# SI4432_Transceiver.net
KiCad netlist of a schematic drawn in Altium Designer
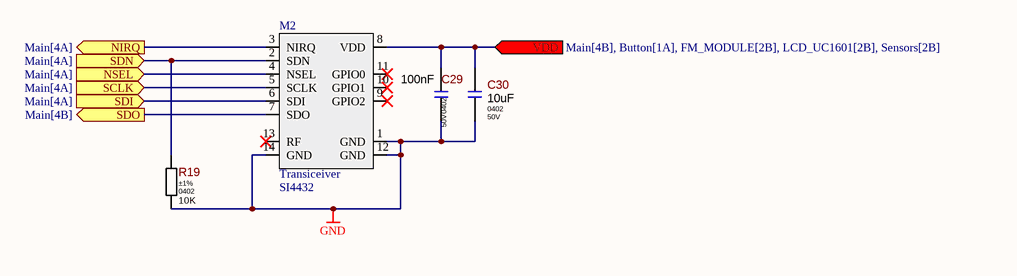
[diagram p0: SI4432_Transceiver.SchDoc]

(export (version "E")
  (design (tool "Eeschema 10.0.6"))
  (components
    (comp (ref "C29")
      (value "100nF")
      (footprint "Cap_0402")
      (description "100nF 50V  ±25% 0402 Ceramic Capacitor")
      (fields
        (field (name "TOLERANCE") "±25%")
        (field (name "PACKAGE") "0402")
        (field (name "VOLTAGE") "50V")
      )
      (libsource (lib "Capacitors") (part "Cap_0402_100nF"))
    )
    (comp (ref "C30")
      (value "10uF")
      (footprint "Cap_0402")
      (description "10uF 50V  ±25% 0402 Ceramic Capacitor")
      (fields
        (field (name "TOLERANCE") "±25%")
        (field (name "PACKAGE") "0402")
        (field (name "VOLTAGE") "50V")
      )
      (libsource (lib "Capacitors") (part "Cap_0402_10uF"))
    )
    (comp (ref "M2")
      (value "Transiceiver")
      (footprint "SI4432")
      (fields (field (name "NAME") "SI4432"))
      (libsource (lib "Module") (part "SI4432"))
    )
    (comp (ref "R19")
      (value "10K")
      (footprint "Res_0402")
      (description "±1% 1/16W 0402")
      (fields
        (field (name "VOLTAGE") "50V")
        (field (name "TOLERANCE") "±1%")
        (field (name "PACKAGE") "0402")
        (field (name "Comment") "Res_0402_10K")
      )
      (libsource (lib "Resistors") (part "Res_0402_10K"))
    )
  )
  (nets
    (net (code "1") (name "/NIRQ") (class "Default")
      (node (ref "M2") (pin "3") (pinfunction "NIRQ_3") (pintype "passive"))
    )
    (net (code "2") (name "/NSEL") (class "Default")
      (node (ref "M2") (pin "4") (pinfunction "NSEL_4") (pintype "passive"))
    )
    (net (code "3") (name "/SCLK") (class "Default")
      (node (ref "M2") (pin "5") (pinfunction "SCLK_5") (pintype "passive"))
    )
    (net (code "4") (name "/SDI") (class "Default")
      (node (ref "M2") (pin "6") (pinfunction "SDI_6") (pintype "passive"))
    )
    (net (code "5") (name "/SDN") (class "Default")
      (node (ref "M2") (pin "2") (pinfunction "SDN_2") (pintype "passive"))
      (node (ref "R19") (pin "1") (pintype "passive"))
    )
    (net (code "6") (name "/SDO") (class "Default")
      (node (ref "M2") (pin "7") (pinfunction "SDO_7") (pintype "passive"))
    )
    (net (code "7") (name "/VDD") (class "Default")
      (node (ref "C29") (pin "1") (pinfunction "1_1") (pintype "passive"))
      (node (ref "C30") (pin "1") (pinfunction "1_1") (pintype "passive"))
      (node (ref "M2") (pin "8") (pinfunction "VDD_8") (pintype "passive"))
    )
    (net (code "8") (name "GND") (class "Default")
      (node (ref "C29") (pin "2") (pinfunction "2_2") (pintype "passive"))
      (node (ref "C30") (pin "2") (pinfunction "2_2") (pintype "passive"))
      (node (ref "M2") (pin "1") (pinfunction "GND_1") (pintype "passive"))
      (node (ref "M2") (pin "12") (pinfunction "GND_12") (pintype "passive"))
      (node (ref "M2") (pin "14") (pinfunction "GND_14") (pintype "passive"))
      (node (ref "R19") (pin "2") (pintype "passive"))
    )
    (net (code "9") (name "unconnected-(M2-GPIO0-Pad11)") (class "Default")
      (node (ref "M2") (pin "11") (pinfunction "GPIO0_11") (pintype "passive+no_connect"))
    )
    (net (code "10") (name "unconnected-(M2-GPIO1-Pad10)") (class "Default")
      (node (ref "M2") (pin "10") (pinfunction "GPIO1_10") (pintype "passive+no_connect"))
    )
    (net (code "11") (name "unconnected-(M2-GPIO2-Pad9)") (class "Default")
      (node (ref "M2") (pin "9") (pinfunction "GPIO2_9") (pintype "passive+no_connect"))
    )
    (net (code "12") (name "unconnected-(M2-RF-Pad13)") (class "Default")
      (node (ref "M2") (pin "13") (pinfunction "RF_13") (pintype "passive+no_connect"))
    )
  )
)
